# FubarinoMini_v12.net
KiCad netlist of a schematic drawn in EAGLE
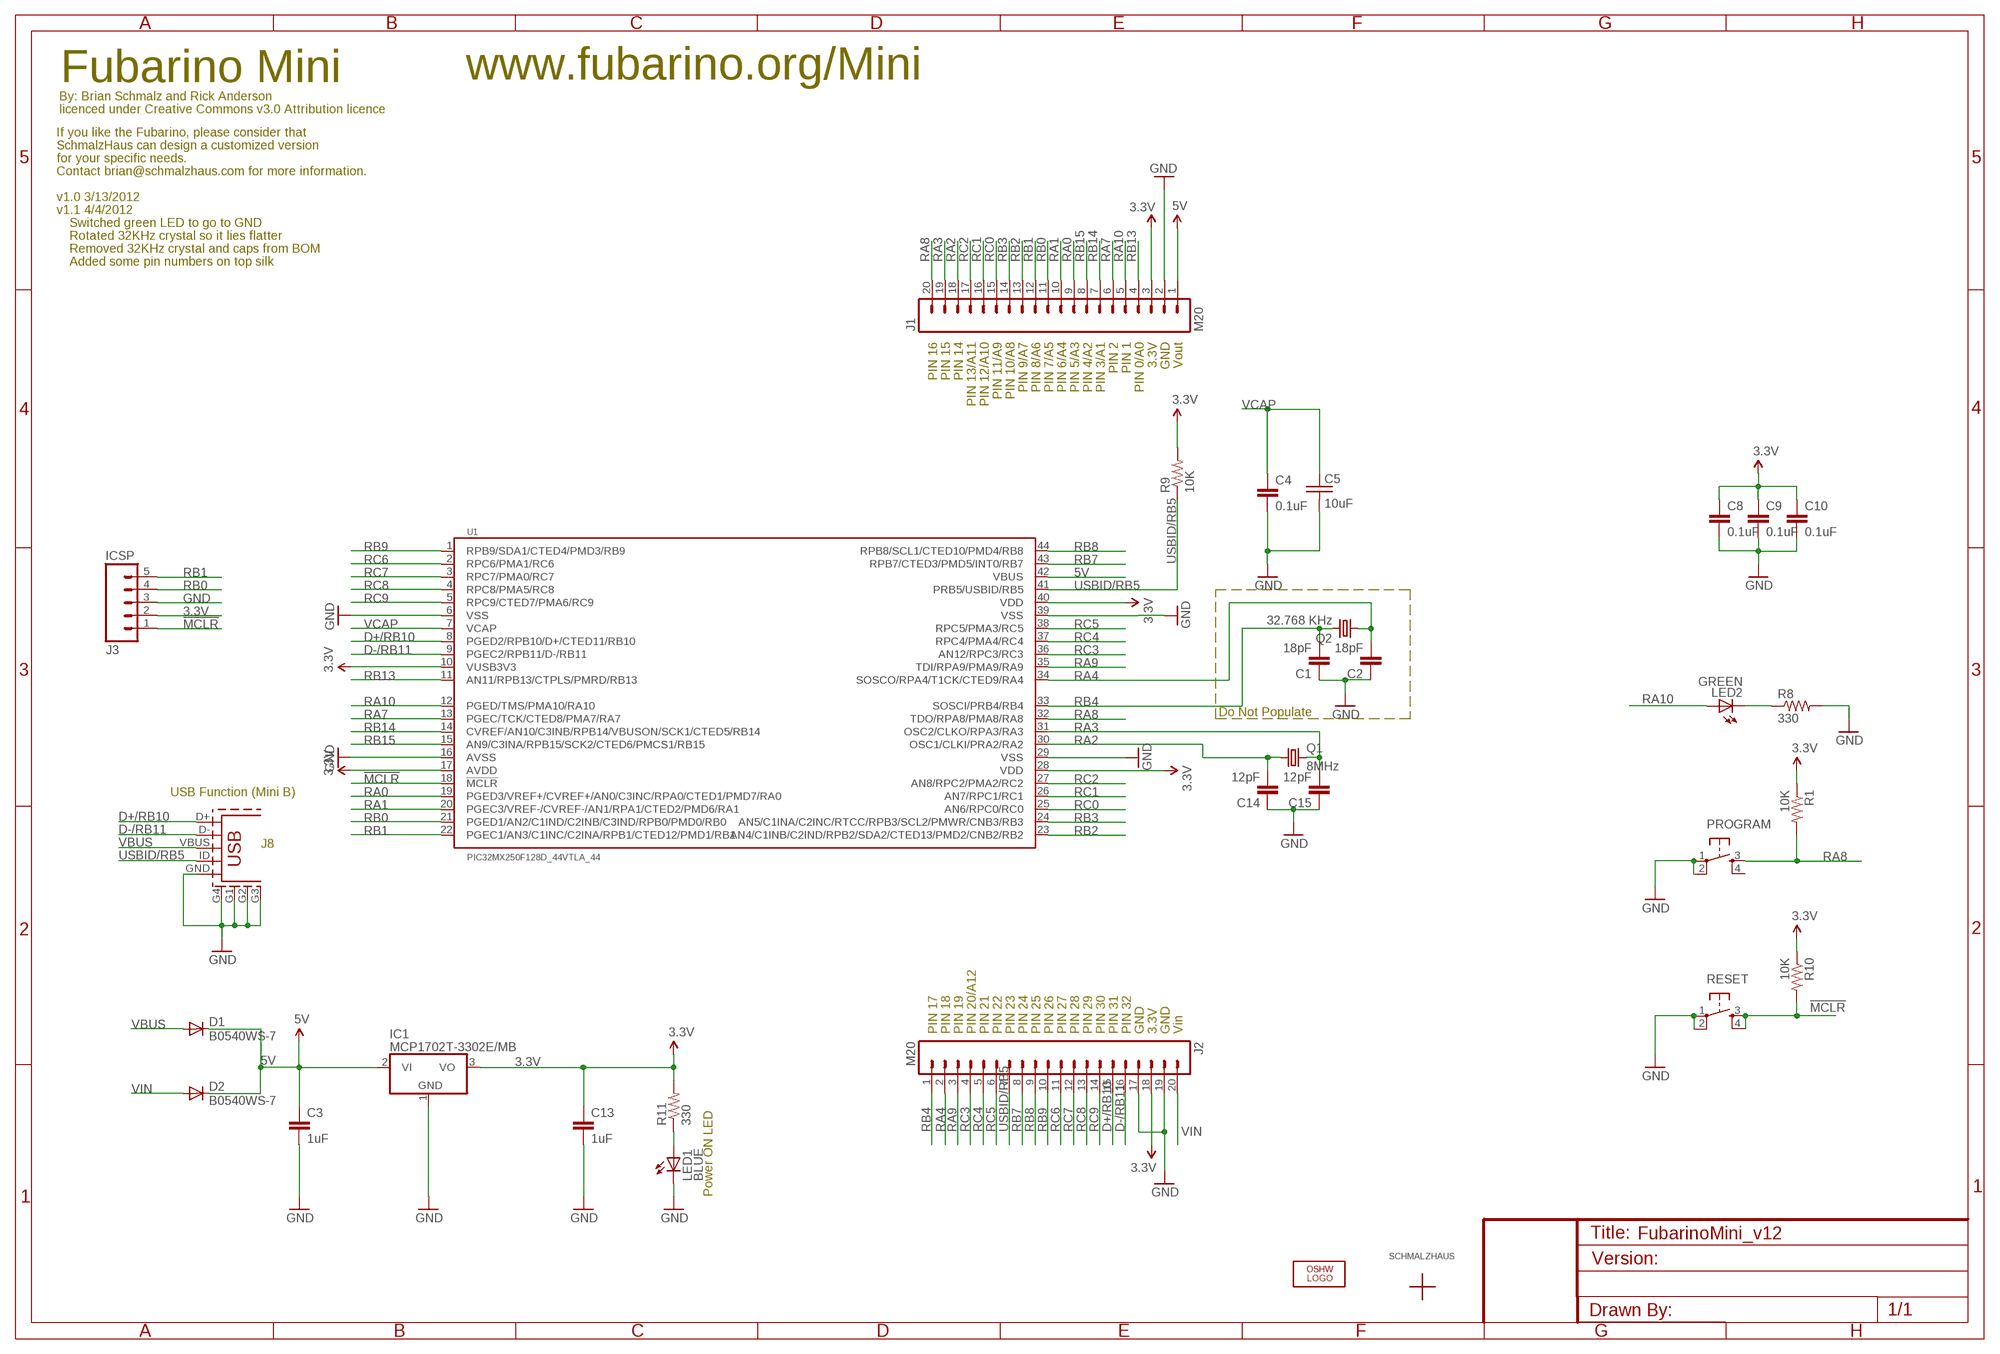
[diagram p0: schematic, sheet 1]

(export (version "E")
  (design (tool "Eeschema 10.0.6"))
  (components
    (comp (ref "C1")
      (value "18pF")
      (footprint "eagle-import:0603-CAP")
      (libsource (lib "eagle-import") (part "CAP0603-CAP"))
    )
    (comp (ref "C2")
      (value "18pF")
      (footprint "eagle-import:0603-CAP")
      (libsource (lib "eagle-import") (part "CAP0603-CAP"))
    )
    (comp (ref "C3")
      (value "1uF")
      (footprint "eagle-import:0603-CAP")
      (libsource (lib "eagle-import") (part "CAP0603-CAP"))
    )
    (comp (ref "C4")
      (value "0.1uF")
      (footprint "eagle-import:0603-CAP")
      (libsource (lib "eagle-import") (part "CAP0603-CAP"))
    )
    (comp (ref "C5")
      (value "10uF")
      (footprint "eagle-import:CAP_0805")
      (libsource (lib "eagle-import") (part "CAP0805"))
    )
    (comp (ref "C8")
      (value "0.1uF")
      (footprint "eagle-import:0603-CAP")
      (libsource (lib "eagle-import") (part "CAP0603-CAP"))
    )
    (comp (ref "C9")
      (value "0.1uF")
      (footprint "eagle-import:0603-CAP")
      (libsource (lib "eagle-import") (part "CAP0603-CAP"))
    )
    (comp (ref "C10")
      (value "0.1uF")
      (footprint "eagle-import:0603")
      (libsource (lib "eagle-import") (part "CAP0603"))
    )
    (comp (ref "C13")
      (value "1uF")
      (footprint "eagle-import:0603")
      (libsource (lib "eagle-import") (part "CAP0603"))
    )
    (comp (ref "C14")
      (value "12pF")
      (footprint "eagle-import:0603-CAP")
      (libsource (lib "eagle-import") (part "CAP0603-CAP"))
    )
    (comp (ref "C15")
      (value "12pF")
      (footprint "eagle-import:0603-CAP")
      (libsource (lib "eagle-import") (part "CAP0603-CAP"))
    )
    (comp (ref "D1")
      (value "B0540WS-7")
      (footprint "eagle-import:SOD-323")
      (libsource (lib "eagle-import") (part "DIODESOD"))
    )
    (comp (ref "D2")
      (value "B0540WS-7")
      (footprint "eagle-import:SOD-323")
      (libsource (lib "eagle-import") (part "DIODESOD"))
    )
    (comp (ref "IC1")
      (value "MCP1702T-3302E/MB")
      (footprint "eagle-import:SOT89")
      (libsource (lib "eagle-import") (part "MCP1703MB33"))
    )
    (comp (ref "ICSP")
      (value "J3")
      (footprint "eagle-import:1X05_NOSILK")
      (libsource (lib "eagle-import") (part "M05NOSLILK"))
    )
    (comp (ref "J1")
      (value "M20")
      (footprint "eagle-import:1X20_NO_PIN1")
      (libsource (lib "eagle-import") (part "M20"))
    )
    (comp (ref "J2")
      (value "M20")
      (footprint "eagle-import:1X20_NO_PIN1")
      (libsource (lib "eagle-import") (part "M20"))
    )
    (comp (ref "J8")
      (value "USB_5PIN")
      (footprint "eagle-import:USB-MINIB")
      (libsource (lib "eagle-import") (part "USB_5PIN"))
    )
    (comp (ref "LED1")
      (value "BLUE")
      (footprint "eagle-import:LED-0603")
      (libsource (lib "eagle-import") (part "LED0603"))
    )
    (comp (ref "LED2")
      (value "GREEN")
      (footprint "eagle-import:LED-0603")
      (libsource (lib "eagle-import") (part "LED0603"))
    )
    (comp (ref "LOGO1")
      (value "OSHW_LOGO_8MILX0070-NT")
      (footprint "eagle-import:OSHW_8X70_NOTEXT")
      (libsource (lib "eagle-import") (part "OSHW_LOGO_8MILX0070-NT"))
    )
    (comp (ref "PROGRAM")
      (value "TAC_SWITCHSND")
      (footprint "eagle-import:TACTILE_SWITCH_SMD")
      (libsource (lib "eagle-import") (part "TAC_SWITCHSND"))
    )
    (comp (ref "Q1")
      (value "8MHz")
      (footprint "eagle-import:NX5032_5MM_3.2MM_CRYSTAL")
      (libsource (lib "eagle-import") (part "CRYSTALNX5032"))
    )
    (comp (ref "Q2")
      (value "32.768 KHz")
      (footprint "eagle-import:TC26H")
      (libsource (lib "eagle-import") (part "CRYSTALTC26H"))
    )
    (comp (ref "R1")
      (value "10K")
      (footprint "eagle-import:0603-RES")
      (libsource (lib "eagle-import") (part "RESISTOR0603-RES"))
    )
    (comp (ref "R8")
      (value "330")
      (footprint "eagle-import:0603-RES")
      (libsource (lib "eagle-import") (part "RESISTOR0603-RES"))
    )
    (comp (ref "R9")
      (value "10K")
      (footprint "eagle-import:0603-RES")
      (libsource (lib "eagle-import") (part "RESISTOR0603-RES"))
    )
    (comp (ref "R10")
      (value "10K")
      (footprint "eagle-import:0603-RES")
      (libsource (lib "eagle-import") (part "RESISTOR0603-RES"))
    )
    (comp (ref "R11")
      (value "330")
      (footprint "eagle-import:0603-RES")
      (libsource (lib "eagle-import") (part "RESISTOR0603-RES"))
    )
    (comp (ref "RESET")
      (value "TAC_SWITCHSND")
      (footprint "eagle-import:TACTILE_SWITCH_SMD")
      (libsource (lib "eagle-import") (part "TAC_SWITCHSND"))
    )
    (comp (ref "U$1")
      (value "SCHMALZHAUSSCHMALZHAUS_SMALL")
      (footprint "eagle-import:SCHMALZHAUS_SMALL")
      (libsource (lib "eagle-import") (part "SCHMALZHAUSSCHMALZHAUS_SMALL"))
    )
    (comp (ref "U1")
      (value "PIC32MX250F128D_44VTLA_44")
      (footprint "eagle-import:VTLA_44")
      (libsource (lib "eagle-import") (part "PIC32MX2XX_44VLA_44"))
    )
  )
  (nets
    (net (code "1") (name "/D+{slash}RB10") (class "Default")
      (node (ref "J2") (pin "15") (pinfunction "15_15") (pintype "passive"))
      (node (ref "J8") (pin "D+") (pinfunction "D+_D+") (pintype "bidirectional"))
      (node (ref "U1") (pin "8") (pinfunction "PGED2/RPB10/D+/CTED11/RB10_8") (pintype "bidirectional"))
    )
    (net (code "2") (name "/D-{slash}RB11") (class "Default")
      (node (ref "J2") (pin "16") (pinfunction "16_16") (pintype "passive"))
      (node (ref "J8") (pin "D-") (pinfunction "D-_D-") (pintype "bidirectional"))
      (node (ref "U1") (pin "9") (pinfunction "PGEC2/RPB11/D-/RB11_9") (pintype "bidirectional"))
    )
    (net (code "3") (name "/RA0") (class "Default")
      (node (ref "J1") (pin "9") (pinfunction "9_9") (pintype "passive"))
      (node (ref "U1") (pin "19") (pinfunction "PGED3/VREF+/CVREF+/AN0/C3INC/RPA0/CTED1/PMD7/RA0_19") (pintype "bidirectional"))
    )
    (net (code "4") (name "/RA1") (class "Default")
      (node (ref "J1") (pin "10") (pinfunction "10_10") (pintype "passive"))
      (node (ref "U1") (pin "20") (pinfunction "PGEC3/VREF-/CVREF-/AN1/RPA1/CTED2/PMD6/RA1_20") (pintype "bidirectional"))
    )
    (net (code "5") (name "/RA2") (class "Default")
      (node (ref "C14") (pin "2") (pinfunction "2_2") (pintype "passive"))
      (node (ref "J1") (pin "18") (pinfunction "18_18") (pintype "passive"))
      (node (ref "Q1") (pin "1") (pinfunction "1_1") (pintype "passive"))
      (node (ref "U1") (pin "30") (pinfunction "OSC1/CLKI/PRA2/RA2_30") (pintype "bidirectional"))
    )
    (net (code "6") (name "/RA3") (class "Default")
      (node (ref "C15") (pin "2") (pinfunction "2_2") (pintype "passive"))
      (node (ref "J1") (pin "19") (pinfunction "19_19") (pintype "passive"))
      (node (ref "Q1") (pin "2") (pinfunction "2_2") (pintype "passive"))
      (node (ref "U1") (pin "31") (pinfunction "OSC2/CLKO/RPA3/RA3_31") (pintype "bidirectional"))
    )
    (net (code "7") (name "/RA4") (class "Default")
      (node (ref "C2") (pin "2") (pinfunction "2_2") (pintype "passive"))
      (node (ref "J2") (pin "2") (pinfunction "2_2") (pintype "passive"))
      (node (ref "Q2") (pin "1") (pinfunction "1_1") (pintype "passive"))
      (node (ref "U1") (pin "34") (pinfunction "SOSCO/RPA4/T1CK/CTED9/RA4_34") (pintype "bidirectional"))
    )
    (net (code "8") (name "/RA7") (class "Default")
      (node (ref "J1") (pin "6") (pinfunction "6_6") (pintype "passive"))
      (node (ref "U1") (pin "13") (pinfunction "PGEC/TCK/CTED8/PMA7/RA7_13") (pintype "bidirectional"))
    )
    (net (code "9") (name "/RA8") (class "Default")
      (node (ref "J1") (pin "20") (pinfunction "20_20") (pintype "passive"))
      (node (ref "PROGRAM") (pin "3") (pinfunction "3_3") (pintype "passive"))
      (node (ref "R1") (pin "2") (pinfunction "2_2") (pintype "passive"))
      (node (ref "U1") (pin "32") (pinfunction "TDO/RPA8/PMA8/RA8_32") (pintype "bidirectional"))
    )
    (net (code "10") (name "/RA9") (class "Default")
      (node (ref "J2") (pin "3") (pinfunction "3_3") (pintype "passive"))
      (node (ref "U1") (pin "35") (pinfunction "TDI/RPA9/PMA9/RA9_35") (pintype "bidirectional"))
    )
    (net (code "11") (name "/RA10") (class "Default")
      (node (ref "J1") (pin "5") (pinfunction "5_5") (pintype "passive"))
      (node (ref "LED2") (pin "A") (pinfunction "A_A") (pintype "passive"))
      (node (ref "U1") (pin "12") (pinfunction "PGED/TMS/PMA10/RA10_12") (pintype "bidirectional"))
    )
    (net (code "12") (name "/RB0") (class "Default")
      (node (ref "ICSP") (pin "4") (pinfunction "4_4") (pintype "passive"))
      (node (ref "J1") (pin "11") (pinfunction "11_11") (pintype "passive"))
      (node (ref "U1") (pin "21") (pinfunction "PGED1/AN2/C1IND/C2INB/C3IND/RPB0/PMD0/RB0_21") (pintype "bidirectional"))
    )
    (net (code "13") (name "/RB1") (class "Default")
      (node (ref "ICSP") (pin "5") (pinfunction "5_5") (pintype "passive"))
      (node (ref "J1") (pin "12") (pinfunction "12_12") (pintype "passive"))
      (node (ref "U1") (pin "22") (pinfunction "PGEC1/AN3/C1INC/C2INA/RPB1/CTED12/PMD1/RB1_22") (pintype "bidirectional"))
    )
    (net (code "14") (name "/RB2") (class "Default")
      (node (ref "J1") (pin "13") (pinfunction "13_13") (pintype "passive"))
      (node (ref "U1") (pin "23") (pinfunction "AN4/C1INB/C2IND/RPB2/SDA2/CTED13/PMD2/CNB2/RB2_23") (pintype "bidirectional"))
    )
    (net (code "15") (name "/RB3") (class "Default")
      (node (ref "J1") (pin "14") (pinfunction "14_14") (pintype "passive"))
      (node (ref "U1") (pin "24") (pinfunction "AN5/C1INA/C2INC/RTCC/RPB3/SCL2/PMWR/CNB3/RB3_24") (pintype "bidirectional"))
    )
    (net (code "16") (name "/RB4") (class "Default")
      (node (ref "C1") (pin "2") (pinfunction "2_2") (pintype "passive"))
      (node (ref "J2") (pin "1") (pinfunction "1_1") (pintype "passive"))
      (node (ref "Q2") (pin "2") (pinfunction "2_2") (pintype "passive"))
      (node (ref "U1") (pin "33") (pinfunction "SOSCI/PRB4/RB4_33") (pintype "bidirectional"))
    )
    (net (code "17") (name "/RB7") (class "Default")
      (node (ref "J2") (pin "8") (pinfunction "8_8") (pintype "passive"))
      (node (ref "U1") (pin "43") (pinfunction "RPB7/CTED3/PMD5/INT0/RB7_43") (pintype "bidirectional"))
    )
    (net (code "18") (name "/RB8") (class "Default")
      (node (ref "J2") (pin "9") (pinfunction "9_9") (pintype "passive"))
      (node (ref "U1") (pin "44") (pinfunction "RPB8/SCL1/CTED10/PMD4/RB8_44") (pintype "bidirectional"))
    )
    (net (code "19") (name "/RB9") (class "Default")
      (node (ref "J2") (pin "10") (pinfunction "10_10") (pintype "passive"))
      (node (ref "U1") (pin "1") (pinfunction "RPB9/SDA1/CTED4/PMD3/RB9_1") (pintype "bidirectional"))
    )
    (net (code "20") (name "/RB13") (class "Default")
      (node (ref "J1") (pin "4") (pinfunction "4_4") (pintype "passive"))
      (node (ref "U1") (pin "11") (pinfunction "AN11/RPB13/CTPLS/PMRD/RB13_11") (pintype "bidirectional"))
    )
    (net (code "21") (name "/RB14") (class "Default")
      (node (ref "J1") (pin "7") (pinfunction "7_7") (pintype "passive"))
      (node (ref "U1") (pin "14") (pinfunction "CVREF/AN10/C3INB/RPB14/VBUSON/SCK1/CTED5/RB14_14") (pintype "bidirectional"))
    )
    (net (code "22") (name "/RB15") (class "Default")
      (node (ref "J1") (pin "8") (pinfunction "8_8") (pintype "passive"))
      (node (ref "U1") (pin "15") (pinfunction "AN9/C3INA/RPB15/SCK2/CTED6/PMCS1/RB15_15") (pintype "bidirectional"))
    )
    (net (code "23") (name "/RC0") (class "Default")
      (node (ref "J1") (pin "15") (pinfunction "15_15") (pintype "passive"))
      (node (ref "U1") (pin "25") (pinfunction "AN6/RPC0/RC0_25") (pintype "bidirectional"))
    )
    (net (code "24") (name "/RC1") (class "Default")
      (node (ref "J1") (pin "16") (pinfunction "16_16") (pintype "passive"))
      (node (ref "U1") (pin "26") (pinfunction "AN7/RPC1/RC1_26") (pintype "bidirectional"))
    )
    (net (code "25") (name "/RC2") (class "Default")
      (node (ref "J1") (pin "17") (pinfunction "17_17") (pintype "passive"))
      (node (ref "U1") (pin "27") (pinfunction "AN8/RPC2/PMA2/RC2_27") (pintype "bidirectional"))
    )
    (net (code "26") (name "/RC3") (class "Default")
      (node (ref "J2") (pin "4") (pinfunction "4_4") (pintype "passive"))
      (node (ref "U1") (pin "36") (pinfunction "AN12/RPC3/RC3_36") (pintype "bidirectional"))
    )
    (net (code "27") (name "/RC4") (class "Default")
      (node (ref "J2") (pin "5") (pinfunction "5_5") (pintype "passive"))
      (node (ref "U1") (pin "37") (pinfunction "RPC4/PMA4/RC4_37") (pintype "bidirectional"))
    )
    (net (code "28") (name "/RC5") (class "Default")
      (node (ref "J2") (pin "6") (pinfunction "6_6") (pintype "passive"))
      (node (ref "U1") (pin "38") (pinfunction "RPC5/PMA3/RC5_38") (pintype "bidirectional"))
    )
    (net (code "29") (name "/RC6") (class "Default")
      (node (ref "J2") (pin "11") (pinfunction "11_11") (pintype "passive"))
      (node (ref "U1") (pin "2") (pinfunction "RPC6/PMA1/RC6_2") (pintype "bidirectional"))
    )
    (net (code "30") (name "/RC7") (class "Default")
      (node (ref "J2") (pin "12") (pinfunction "12_12") (pintype "passive"))
      (node (ref "U1") (pin "3") (pinfunction "RPC7/PMA0/RC7_3") (pintype "bidirectional"))
    )
    (net (code "31") (name "/RC8") (class "Default")
      (node (ref "J2") (pin "13") (pinfunction "13_13") (pintype "passive"))
      (node (ref "U1") (pin "4") (pinfunction "RPC8/PMA5/RC8_4") (pintype "bidirectional"))
    )
    (net (code "32") (name "/RC9") (class "Default")
      (node (ref "J2") (pin "14") (pinfunction "14_14") (pintype "passive"))
      (node (ref "U1") (pin "5") (pinfunction "RPC9/CTED7/PMA6/RC9_5") (pintype "bidirectional"))
    )
    (net (code "33") (name "/USBID{slash}RB5") (class "Default")
      (node (ref "J2") (pin "7") (pinfunction "7_7") (pintype "passive"))
      (node (ref "J8") (pin "ID") (pinfunction "USB_ID_ID") (pintype "bidirectional"))
      (node (ref "R9") (pin "1") (pinfunction "1_1") (pintype "passive"))
      (node (ref "U1") (pin "41") (pinfunction "PRB5/USBID/RB5_41") (pintype "bidirectional"))
    )
    (net (code "34") (name "/VBUS") (class "Default")
      (node (ref "D1") (pin "2") (pinfunction "A_2") (pintype "passive"))
      (node (ref "J8") (pin "VBUS") (pinfunction "VBUS_VBUS") (pintype "bidirectional"))
    )
    (net (code "35") (name "/VCAP") (class "Default")
      (node (ref "C4") (pin "1") (pinfunction "1_1") (pintype "passive"))
      (node (ref "C5") (pin "1") (pinfunction "1_1") (pintype "passive"))
      (node (ref "U1") (pin "7") (pinfunction "VCAP_7") (pintype "bidirectional"))
    )
    (net (code "36") (name "/VIN") (class "Default")
      (node (ref "D2") (pin "2") (pinfunction "A_2") (pintype "passive"))
      (node (ref "J2") (pin "20") (pinfunction "20_20") (pintype "passive"))
    )
    (net (code "37") (name "/~{MCLR}") (class "Default")
      (node (ref "ICSP") (pin "1") (pinfunction "1_1") (pintype "passive"))
      (node (ref "R10") (pin "2") (pinfunction "2_2") (pintype "passive"))
      (node (ref "RESET") (pin "3") (pinfunction "3_3") (pintype "passive"))
      (node (ref "RESET") (pin "4") (pinfunction "4_4") (pintype "passive"))
      (node (ref "U1") (pin "18") (pinfunction "~{MCLR}_18") (pintype "bidirectional"))
    )
    (net (code "38") (name "3.3V") (class "Default")
      (node (ref "C10") (pin "1") (pinfunction "1_1") (pintype "passive"))
      (node (ref "C13") (pin "1") (pinfunction "1_1") (pintype "passive"))
      (node (ref "C8") (pin "1") (pinfunction "1_1") (pintype "passive"))
      (node (ref "C9") (pin "1") (pinfunction "1_1") (pintype "passive"))
      (node (ref "IC1") (pin "3") (pinfunction "VO_3") (pintype "passive"))
      (node (ref "ICSP") (pin "2") (pinfunction "2_2") (pintype "passive"))
      (node (ref "J1") (pin "3") (pinfunction "3_3") (pintype "passive"))
      (node (ref "J2") (pin "18") (pinfunction "18_18") (pintype "passive"))
      (node (ref "R1") (pin "1") (pinfunction "1_1") (pintype "passive"))
      (node (ref "R10") (pin "1") (pinfunction "1_1") (pintype "passive"))
      (node (ref "R11") (pin "2") (pinfunction "2_2") (pintype "passive"))
      (node (ref "R9") (pin "2") (pinfunction "2_2") (pintype "passive"))
      (node (ref "U1") (pin "10") (pinfunction "VUSB3V3_10") (pintype "bidirectional"))
      (node (ref "U1") (pin "17") (pinfunction "AVDD_17") (pintype "bidirectional"))
      (node (ref "U1") (pin "28") (pinfunction "VDD_28") (pintype "bidirectional"))
      (node (ref "U1") (pin "40") (pinfunction "VDD_40") (pintype "bidirectional"))
    )
    (net (code "39") (name "5V") (class "Default")
      (node (ref "C3") (pin "1") (pinfunction "1_1") (pintype "passive"))
      (node (ref "D1") (pin "1") (pinfunction "C_1") (pintype "passive"))
      (node (ref "D2") (pin "1") (pinfunction "C_1") (pintype "passive"))
      (node (ref "IC1") (pin "2") (pinfunction "VI_2") (pintype "input"))
      (node (ref "IC1") (pin "2@1") (pinfunction "VI1_2@1") (pintype "input"))
      (node (ref "J1") (pin "1") (pinfunction "1_1") (pintype "passive"))
      (node (ref "U1") (pin "42") (pinfunction "VBUS_42") (pintype "bidirectional"))
    )
    (net (code "40") (name "GND") (class "Default")
      (node (ref "C1") (pin "1") (pinfunction "1_1") (pintype "passive"))
      (node (ref "C10") (pin "2") (pinfunction "2_2") (pintype "passive"))
      (node (ref "C13") (pin "2") (pinfunction "2_2") (pintype "passive"))
      (node (ref "C14") (pin "1") (pinfunction "1_1") (pintype "passive"))
      (node (ref "C15") (pin "1") (pinfunction "1_1") (pintype "passive"))
      (node (ref "C2") (pin "1") (pinfunction "1_1") (pintype "passive"))
      (node (ref "C3") (pin "2") (pinfunction "2_2") (pintype "passive"))
      (node (ref "C4") (pin "2") (pinfunction "2_2") (pintype "passive"))
      (node (ref "C5") (pin "2") (pinfunction "2_2") (pintype "passive"))
      (node (ref "C8") (pin "2") (pinfunction "2_2") (pintype "passive"))
      (node (ref "C9") (pin "2") (pinfunction "2_2") (pintype "passive"))
      (node (ref "IC1") (pin "1") (pinfunction "GND_1") (pintype "passive"))
      (node (ref "ICSP") (pin "3") (pinfunction "3_3") (pintype "passive"))
      (node (ref "J1") (pin "2") (pinfunction "2_2") (pintype "passive"))
      (node (ref "J2") (pin "17") (pinfunction "17_17") (pintype "passive"))
      (node (ref "J2") (pin "19") (pinfunction "19_19") (pintype "passive"))
      (node (ref "J8") (pin "G1") (pinfunction "P$1_G1") (pintype "bidirectional"))
      (node (ref "J8") (pin "G2") (pinfunction "P$2_G2") (pintype "bidirectional"))
      (node (ref "J8") (pin "G3") (pinfunction "P$3_G3") (pintype "bidirectional"))
      (node (ref "J8") (pin "G4") (pinfunction "SHIELD_G4") (pintype "bidirectional"))
      (node (ref "J8") (pin "GND") (pinfunction "GND_GND") (pintype "bidirectional"))
      (node (ref "LED1") (pin "C") (pinfunction "C_C") (pintype "passive"))
      (node (ref "PROGRAM") (pin "1") (pinfunction "1_1") (pintype "passive"))
      (node (ref "PROGRAM") (pin "2") (pinfunction "2_2") (pintype "passive"))
      (node (ref "R8") (pin "2") (pinfunction "2_2") (pintype "passive"))
      (node (ref "RESET") (pin "1") (pinfunction "1_1") (pintype "passive"))
      (node (ref "RESET") (pin "2") (pinfunction "2_2") (pintype "passive"))
      (node (ref "U1") (pin "16") (pinfunction "AVSS_16") (pintype "bidirectional"))
      (node (ref "U1") (pin "29") (pinfunction "VSS_29") (pintype "bidirectional"))
      (node (ref "U1") (pin "39") (pinfunction "VSS_39") (pintype "bidirectional"))
      (node (ref "U1") (pin "6") (pinfunction "VSS_6") (pintype "bidirectional"))
    )
    (net (code "41") (name "Net-(LED1-PadA)") (class "Default")
      (node (ref "LED1") (pin "A") (pinfunction "A_A") (pintype "passive"))
      (node (ref "R11") (pin "1") (pinfunction "1_1") (pintype "passive"))
    )
    (net (code "42") (name "Net-(LED2-PadC)") (class "Default")
      (node (ref "LED2") (pin "C") (pinfunction "C_C") (pintype "passive"))
      (node (ref "R8") (pin "1") (pinfunction "1_1") (pintype "passive"))
    )
    (net (code "43") (name "unconnected-(PROGRAM-Pad4)") (class "Default")
      (node (ref "PROGRAM") (pin "4") (pinfunction "4_4") (pintype "passive"))
    )
  )
)
